# GSMMHM.net
KiCad netlist of a schematic drawn in Altium Designer
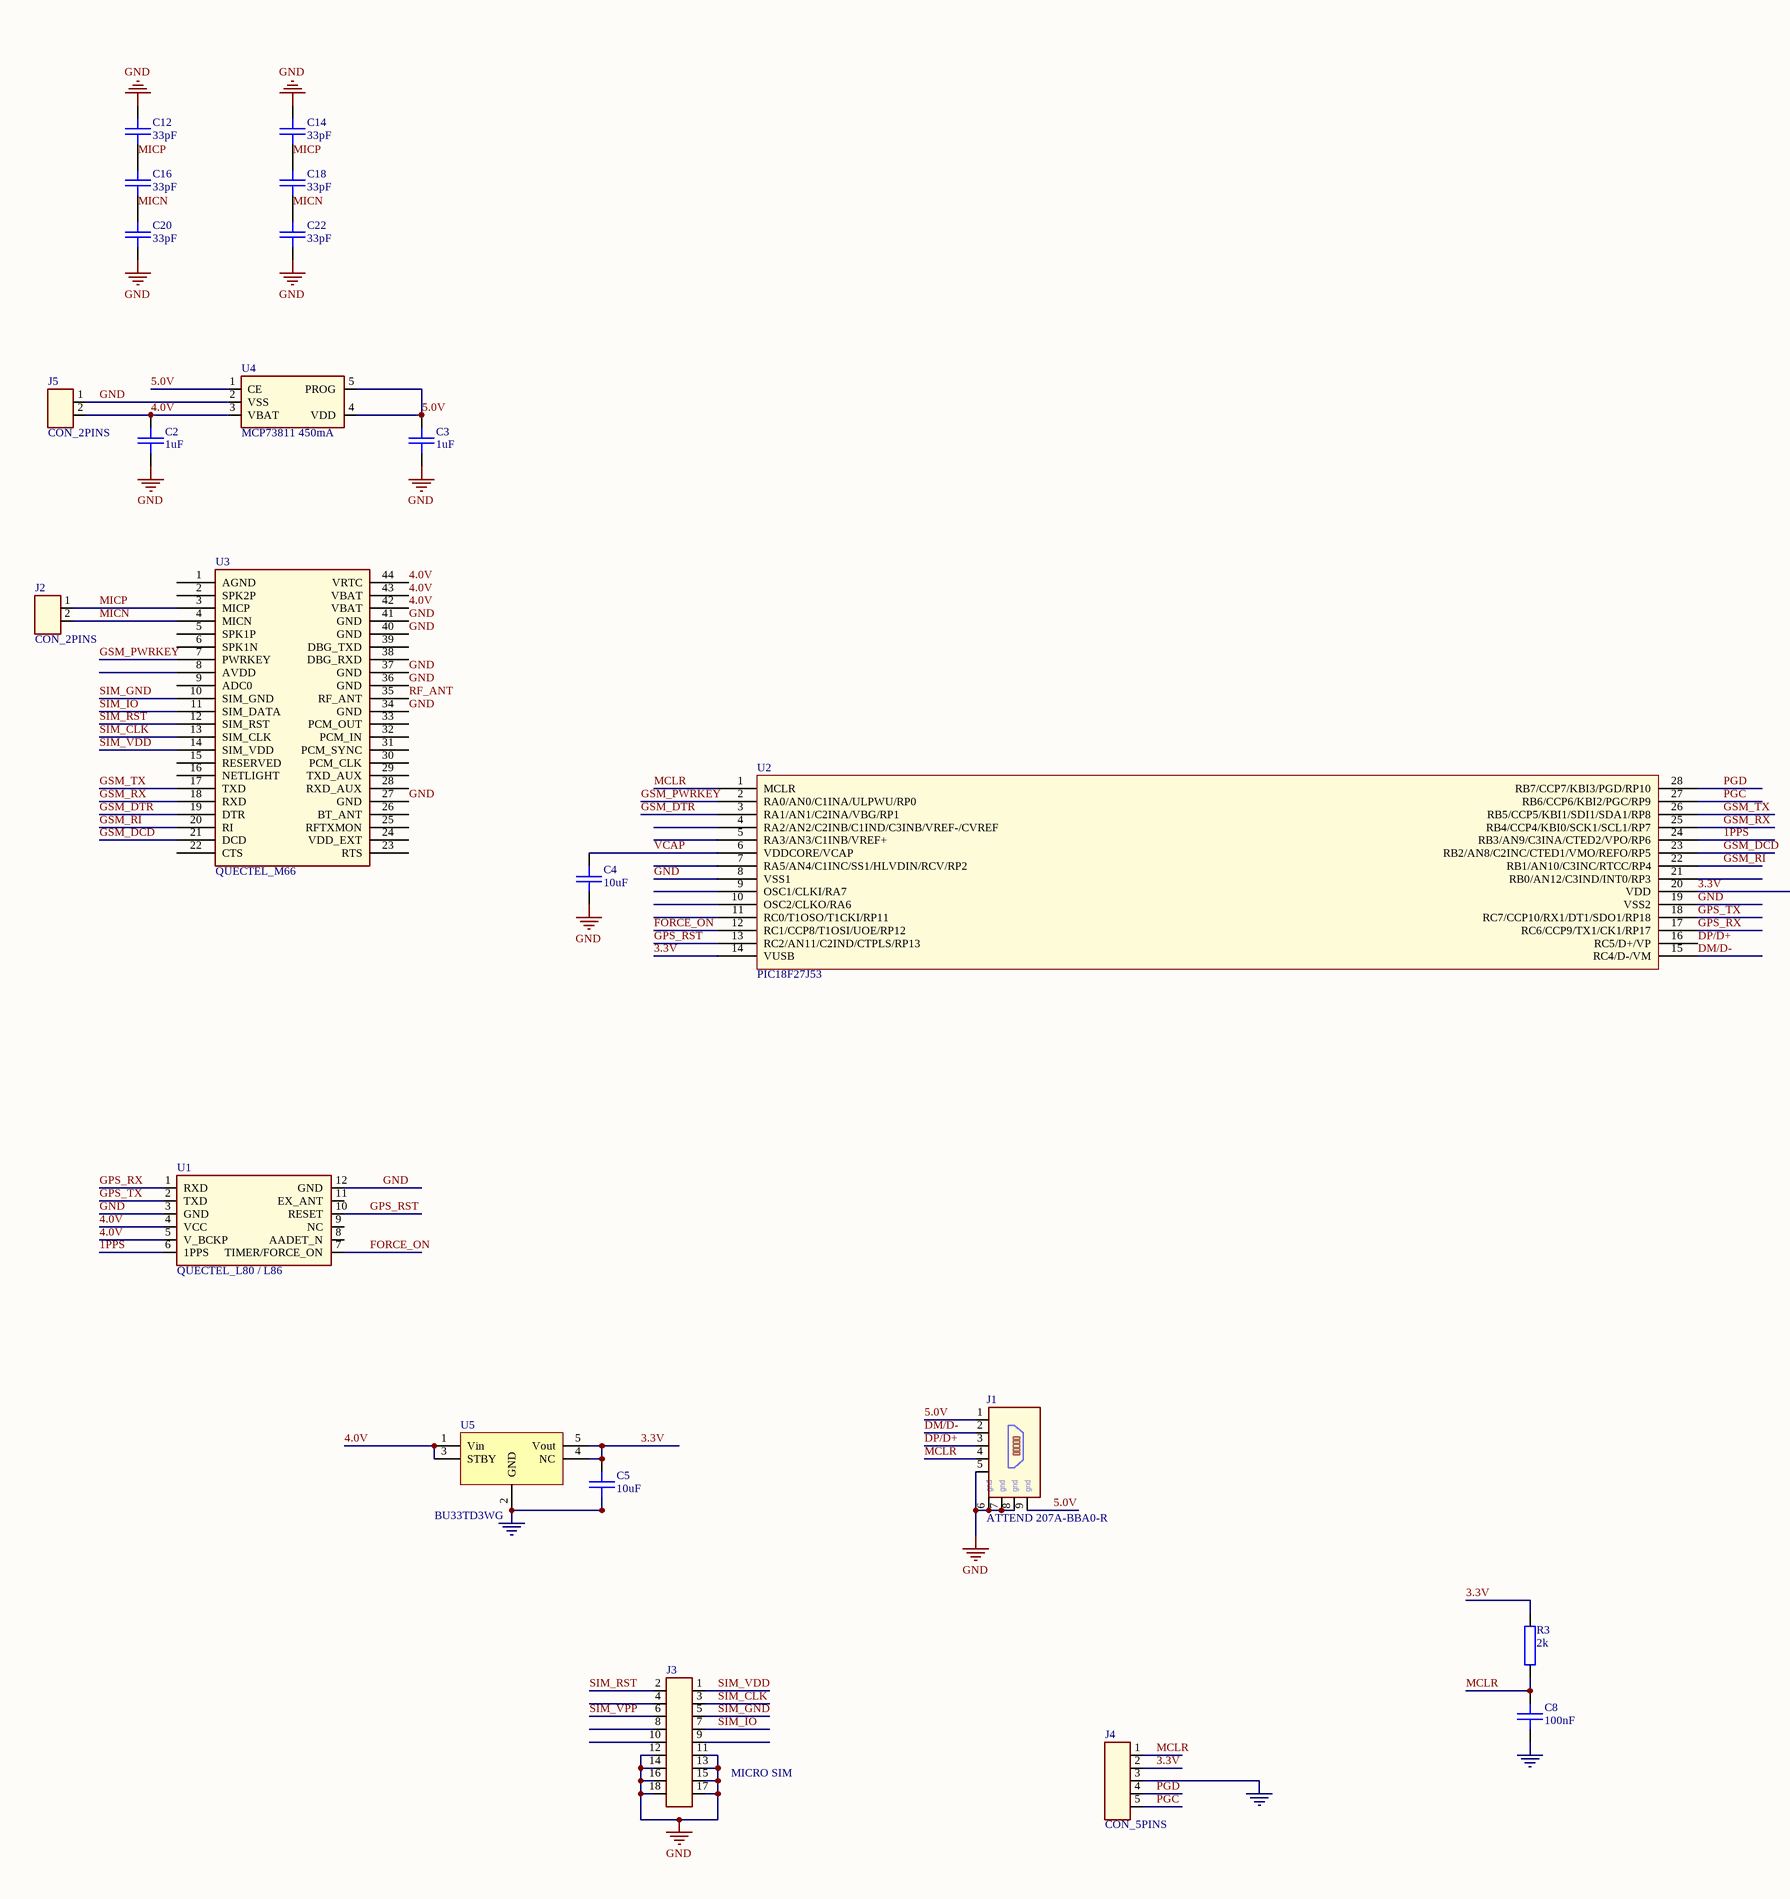
[diagram p0: GSMMHM.SchDoc, left]
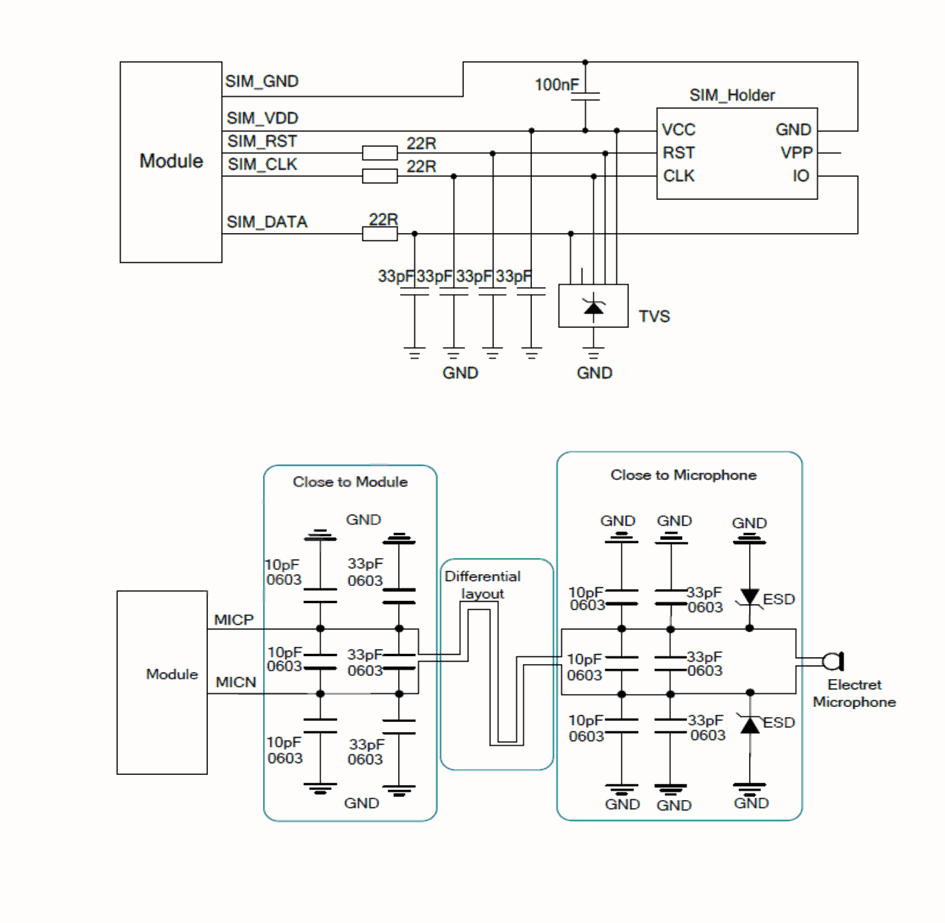
[diagram p1: GSMMHM.SchDoc, right]

(export (version "E")
  (design (tool "Eeschema 10.0.6"))
  (components
    (comp (ref "C2") (value "1uF") (footprint "SMD_0603_CAPC1608X95N") (libsource (lib "DLV") (part "C")))
    (comp (ref "C3") (value "1uF") (footprint "SMD_0603_CAPC1608X95N") (libsource (lib "DLV") (part "C")))
    (comp (ref "C4") (value "10uF") (footprint "SMD_0805_CAPC2012X95N") (libsource (lib "DLV") (part "C")))
    (comp (ref "C5") (value "10uF") (footprint "SMD_0805_CAPC2012X95N") (libsource (lib "DLV") (part "C")))
    (comp (ref "C8") (value "100nF") (footprint "SMD_0603_CAPC1608X95N") (libsource (lib "DLV") (part "C")))
    (comp (ref "C12") (value "33pF") (footprint "SMD_0603_CAPC1608X95N") (libsource (lib "DLV") (part "C")))
    (comp (ref "C14") (value "33pF") (footprint "SMD_0603_CAPC1608X95N") (libsource (lib "DLV") (part "C")))
    (comp (ref "C16") (value "33pF") (footprint "SMD_0603_CAPC1608X95N") (libsource (lib "DLV") (part "C")))
    (comp (ref "C18") (value "33pF") (footprint "SMD_0603_CAPC1608X95N") (libsource (lib "DLV") (part "C")))
    (comp (ref "C20") (value "33pF") (footprint "SMD_0603_CAPC1608X95N") (libsource (lib "DLV") (part "C")))
    (comp (ref "C22") (value "33pF") (footprint "SMD_0603_CAPC1608X95N") (libsource (lib "DLV") (part "C")))
    (comp (ref "J1")
      (value "ATTEND 207A-BBA0-R")
      (footprint "SMD_CON_MICRO_USB")
      (libsource (lib "DLV") (part "CON_USB_MINI"))
    )
    (comp (ref "J2")
      (value "CON_2PINS")
      (footprint "PTH_MIC_6MM_2.7MM_PITCH1.9")
      (libsource (lib "DLV") (part "CON_2PINS"))
    )
    (comp (ref "J3")
      (value "MICRO SIM")
      (footprint "SMD_CON-WURTH_MICRO_SIM_693021010811")
      (libsource (lib "DLV") (part "CON_2ROWS_18PINS"))
    )
    (comp (ref "J4") (value "CON_5PINS") (footprint "SIP5 - PGM") (libsource (lib "DLV") (part "CON_5PINS")))
    (comp (ref "J5")
      (value "CON_2PINS")
      (footprint "PTH_HDRV02W64P254_1X02")
      (libsource (lib "DLV") (part "CON_2PINS"))
    )
    (comp (ref "R3") (value "2k") (footprint "SMD_0603_RESC1608X55N") (libsource (lib "DLV") (part "R")))
    (comp (ref "U1")
      (value "QUECTEL_L80 / L86")
      (footprint "SMD_MOD_L80_SOIC254P1600X1600-12N")
      (libsource (lib "DLV") (part "MOD_QUECTEL_L80_L86"))
    )
    (comp (ref "U2")
      (value "PIC18F27J53")
      (footprint "SMD_SOP65P780X200-28N")
      (libsource (lib "DLV") (part "IC_PIC18F27J53"))
    )
    (comp (ref "U3")
      (value "QUECTEL_M66")
      (footprint "SMD_MOD_M66-44N")
      (libsource (lib "DLV") (part "MOD_QUECTEL_M66"))
    )
    (comp (ref "U4")
      (value "MCP73811 450mA")
      (footprint "SMD_SOT26_SOT95P285X140-5N - DLV")
      (description "MCP73812")
      (fields
        (field (name "DB_PART_NUMBER") "PSU000000127")
        (field (name "DB_MANUFACTURER_PART") "ROHM        BD33KA5WF-E2")
        (field (name "DB_APPROVED_BY") "VSN")
      )
      (libsource (lib "DLV") (part "IC_MCP73812"))
    )
    (comp (ref "U5")
      (value "BU33TD3WG")
      (footprint "SMD_SOT26_SOT95P285X140-5N - DLV")
      (libsource (lib "DLV") (part "IC_BU33TD3WG"))
    )
  )
  (nets
    (net (code "1") (name "/1PPS") (class "Default")
      (node (ref "U1") (pin "6") (pinfunction "1PPS_6") (pintype "passive"))
      (node (ref "U2") (pin "24") (pinfunction "RB3/AN9/C3INA/CTED2/VPO/RP6_24") (pintype "passive"))
    )
    (net (code "2") (name "/3.3V") (class "Default")
      (node (ref "C5") (pin "1") (pinfunction "1_1") (pintype "passive"))
      (node (ref "J4") (pin "2") (pinfunction "2_2") (pintype "passive"))
      (node (ref "R3") (pin "1") (pinfunction "1_1") (pintype "passive"))
      (node (ref "U2") (pin "14") (pinfunction "VUSB_14") (pintype "passive"))
      (node (ref "U2") (pin "20") (pinfunction "VDD_20") (pintype "passive"))
      (node (ref "U5") (pin "4") (pinfunction "NC_4") (pintype "passive"))
      (node (ref "U5") (pin "5") (pinfunction "Vout_5") (pintype "passive"))
    )
    (net (code "3") (name "/4.0V") (class "Default")
      (node (ref "C2") (pin "1") (pinfunction "1_1") (pintype "passive"))
      (node (ref "J5") (pin "2") (pinfunction "2_2") (pintype "passive"))
      (node (ref "U1") (pin "4") (pinfunction "VCC_4") (pintype "passive"))
      (node (ref "U1") (pin "5") (pinfunction "V_BCKP_5") (pintype "passive"))
      (node (ref "U3") (pin "42") (pinfunction "VBAT_42") (pintype "passive"))
      (node (ref "U3") (pin "43") (pinfunction "VBAT_43") (pintype "passive"))
      (node (ref "U3") (pin "44") (pinfunction "VRTC_44") (pintype "passive"))
      (node (ref "U4") (pin "3") (pinfunction "VBAT_3") (pintype "passive"))
      (node (ref "U5") (pin "1") (pinfunction "Vin_1") (pintype "passive"))
      (node (ref "U5") (pin "3") (pinfunction "STBY_3") (pintype "passive"))
    )
    (net (code "4") (name "/5.0V") (class "Default")
      (node (ref "C3") (pin "1") (pinfunction "1_1") (pintype "passive"))
      (node (ref "J1") (pin "1") (pinfunction "1_1") (pintype "passive"))
      (node (ref "J1") (pin "9") (pinfunction "9_9") (pintype "passive"))
      (node (ref "U4") (pin "1") (pinfunction "CE_1") (pintype "passive"))
      (node (ref "U4") (pin "4") (pinfunction "VDD_4") (pintype "passive"))
      (node (ref "U4") (pin "5") (pinfunction "PROG_5") (pintype "passive"))
    )
    (net (code "5") (name "/DM{slash}D-") (class "Default")
      (node (ref "J1") (pin "2") (pinfunction "2_2") (pintype "passive"))
      (node (ref "U2") (pin "15") (pinfunction "RC4/D-/VM_15") (pintype "passive"))
    )
    (net (code "6") (name "/DP{slash}D+") (class "Default")
      (node (ref "J1") (pin "3") (pinfunction "3_3") (pintype "passive"))
      (node (ref "U2") (pin "16") (pinfunction "RC5/D+/VP_16") (pintype "passive"))
    )
    (net (code "7") (name "/FORCE_ON") (class "Default")
      (node (ref "U1") (pin "7") (pinfunction "TIMER/FORCE_ON_7") (pintype "passive"))
      (node (ref "U2") (pin "12") (pinfunction "RC1/CCP8/T1OSI/UOE/RP12_12") (pintype "passive"))
    )
    (net (code "8") (name "/GPS_RST") (class "Default")
      (node (ref "U1") (pin "10") (pinfunction "RESET_10") (pintype "passive"))
      (node (ref "U2") (pin "13") (pinfunction "RC2/AN11/C2IND/CTPLS/RP13_13") (pintype "passive"))
    )
    (net (code "9") (name "/GPS_RX") (class "Default")
      (node (ref "U1") (pin "1") (pinfunction "RXD_1") (pintype "passive"))
      (node (ref "U2") (pin "17") (pinfunction "RC6/CCP9/TX1/CK1/RP17_17") (pintype "passive"))
    )
    (net (code "10") (name "/GPS_TX") (class "Default")
      (node (ref "U1") (pin "2") (pinfunction "TXD_2") (pintype "passive"))
      (node (ref "U2") (pin "18") (pinfunction "RC7/CCP10/RX1/DT1/SDO1/RP18_18") (pintype "passive"))
    )
    (net (code "11") (name "/GSM_DCD") (class "Default")
      (node (ref "U2") (pin "23") (pinfunction "RB2/AN8/C2INC/CTED1/VMO/REFO/RP5_23") (pintype "passive"))
      (node (ref "U3") (pin "21") (pinfunction "DCD_21") (pintype "passive"))
    )
    (net (code "12") (name "/GSM_DTR") (class "Default")
      (node (ref "U2") (pin "3") (pinfunction "RA1/AN1/C2INA/VBG/RP1_3") (pintype "passive"))
      (node (ref "U3") (pin "19") (pinfunction "DTR_19") (pintype "passive"))
    )
    (net (code "13") (name "/GSM_PWRKEY") (class "Default")
      (node (ref "U2") (pin "2") (pinfunction "RA0/AN0/C1INA/ULPWU/RP0_2") (pintype "passive"))
      (node (ref "U3") (pin "7") (pinfunction "PWRKEY_7") (pintype "passive"))
    )
    (net (code "14") (name "/GSM_RI") (class "Default")
      (node (ref "U2") (pin "22") (pinfunction "RB1/AN10/C3INC/RTCC/RP4_22") (pintype "passive"))
      (node (ref "U3") (pin "20") (pinfunction "RI_20") (pintype "passive"))
    )
    (net (code "15") (name "/GSM_RX") (class "Default")
      (node (ref "U2") (pin "25") (pinfunction "RB4/CCP4/KBI0/SCK1/SCL1/RP7_25") (pintype "passive"))
      (node (ref "U3") (pin "18") (pinfunction "RXD_18") (pintype "passive"))
    )
    (net (code "16") (name "/GSM_TX") (class "Default")
      (node (ref "U2") (pin "26") (pinfunction "RB5/CCP5/KBI1/SDI1/SDA1/RP8_26") (pintype "passive"))
      (node (ref "U3") (pin "17") (pinfunction "TXD_17") (pintype "passive"))
    )
    (net (code "17") (name "/MCLR") (class "Default")
      (node (ref "C8") (pin "1") (pinfunction "1_1") (pintype "passive"))
      (node (ref "J1") (pin "4") (pinfunction "4_4") (pintype "passive"))
      (node (ref "J4") (pin "1") (pinfunction "1_1") (pintype "passive"))
      (node (ref "R3") (pin "2") (pinfunction "2_2") (pintype "passive"))
      (node (ref "U2") (pin "1") (pinfunction "MCLR_1") (pintype "passive"))
    )
    (net (code "18") (name "/MICN") (class "Default")
      (node (ref "C16") (pin "2") (pinfunction "2_2") (pintype "passive"))
      (node (ref "C18") (pin "2") (pinfunction "2_2") (pintype "passive"))
      (node (ref "C20") (pin "1") (pinfunction "1_1") (pintype "passive"))
      (node (ref "C22") (pin "1") (pinfunction "1_1") (pintype "passive"))
      (node (ref "J2") (pin "2") (pinfunction "2_2") (pintype "passive"))
      (node (ref "U3") (pin "4") (pinfunction "MICN_4") (pintype "passive"))
    )
    (net (code "19") (name "/MICP") (class "Default")
      (node (ref "C12") (pin "2") (pinfunction "2_2") (pintype "passive"))
      (node (ref "C14") (pin "2") (pinfunction "2_2") (pintype "passive"))
      (node (ref "C16") (pin "1") (pinfunction "1_1") (pintype "passive"))
      (node (ref "C18") (pin "1") (pinfunction "1_1") (pintype "passive"))
      (node (ref "J2") (pin "1") (pinfunction "1_1") (pintype "passive"))
      (node (ref "U3") (pin "3") (pinfunction "MICP_3") (pintype "passive"))
    )
    (net (code "20") (name "/PGC") (class "Default")
      (node (ref "J4") (pin "5") (pinfunction "5_5") (pintype "passive"))
      (node (ref "U2") (pin "27") (pinfunction "RB6/CCP6/KBI2/PGC/RP9_27") (pintype "passive"))
    )
    (net (code "21") (name "/PGD") (class "Default")
      (node (ref "J4") (pin "4") (pinfunction "4_4") (pintype "passive"))
      (node (ref "U2") (pin "28") (pinfunction "RB7/CCP7/KBI3/PGD/RP10_28") (pintype "passive"))
    )
    (net (code "22") (name "/RF_ANT") (class "Default")
      (node (ref "U3") (pin "35") (pinfunction "RF_ANT_35") (pintype "passive"))
    )
    (net (code "23") (name "/SIM_CLK") (class "Default")
      (node (ref "J3") (pin "3") (pinfunction "3_3") (pintype "passive"))
      (node (ref "U3") (pin "13") (pinfunction "SIM_CLK_13") (pintype "passive"))
    )
    (net (code "24") (name "/SIM_GND") (class "Default")
      (node (ref "J3") (pin "5") (pinfunction "5_5") (pintype "passive"))
      (node (ref "U3") (pin "10") (pinfunction "SIM_GND_10") (pintype "passive"))
    )
    (net (code "25") (name "/SIM_IO") (class "Default")
      (node (ref "J3") (pin "7") (pinfunction "7_7") (pintype "passive"))
      (node (ref "U3") (pin "11") (pinfunction "SIM_DATA_11") (pintype "passive"))
    )
    (net (code "26") (name "/SIM_RST") (class "Default")
      (node (ref "J3") (pin "2") (pinfunction "2_2") (pintype "passive"))
      (node (ref "U3") (pin "12") (pinfunction "SIM_RST_12") (pintype "passive"))
    )
    (net (code "27") (name "/SIM_VDD") (class "Default")
      (node (ref "J3") (pin "1") (pinfunction "1_1") (pintype "passive"))
      (node (ref "U3") (pin "14") (pinfunction "SIM_VDD_14") (pintype "passive"))
    )
    (net (code "28") (name "/SIM_VPP") (class "Default")
      (node (ref "J3") (pin "6") (pinfunction "6_6") (pintype "passive"))
    )
    (net (code "29") (name "/VCAP") (class "Default")
      (node (ref "C4") (pin "1") (pinfunction "1_1") (pintype "passive"))
      (node (ref "U2") (pin "6") (pinfunction "VDDCORE/VCAP_6") (pintype "passive"))
    )
    (net (code "30") (name "GND") (class "Default")
      (node (ref "C12") (pin "1") (pinfunction "1_1") (pintype "passive"))
      (node (ref "C14") (pin "1") (pinfunction "1_1") (pintype "passive"))
      (node (ref "C2") (pin "2") (pinfunction "2_2") (pintype "passive"))
      (node (ref "C20") (pin "2") (pinfunction "2_2") (pintype "passive"))
      (node (ref "C22") (pin "2") (pinfunction "2_2") (pintype "passive"))
      (node (ref "C3") (pin "2") (pinfunction "2_2") (pintype "passive"))
      (node (ref "C4") (pin "2") (pinfunction "2_2") (pintype "passive"))
      (node (ref "C5") (pin "2") (pinfunction "2_2") (pintype "passive"))
      (node (ref "C8") (pin "2") (pinfunction "2_2") (pintype "passive"))
      (node (ref "J1") (pin "5") (pinfunction "5_5") (pintype "passive"))
      (node (ref "J1") (pin "6") (pinfunction "6_6") (pintype "passive"))
      (node (ref "J1") (pin "7") (pinfunction "7_7") (pintype "passive"))
      (node (ref "J1") (pin "8") (pinfunction "8_8") (pintype "passive"))
      (node (ref "J3") (pin "11") (pinfunction "11_11") (pintype "passive"))
      (node (ref "J3") (pin "12") (pinfunction "12_12") (pintype "passive"))
      (node (ref "J3") (pin "13") (pinfunction "13_13") (pintype "passive"))
      (node (ref "J3") (pin "14") (pinfunction "14_14") (pintype "passive"))
      (node (ref "J3") (pin "15") (pinfunction "15_15") (pintype "passive"))
      (node (ref "J3") (pin "16") (pinfunction "16_16") (pintype "passive"))
      (node (ref "J3") (pin "17") (pinfunction "17_17") (pintype "passive"))
      (node (ref "J3") (pin "18") (pinfunction "18_18") (pintype "passive"))
      (node (ref "J4") (pin "3") (pinfunction "3_3") (pintype "passive"))
      (node (ref "J5") (pin "1") (pinfunction "1_1") (pintype "passive"))
      (node (ref "U1") (pin "12") (pinfunction "GND_12") (pintype "passive"))
      (node (ref "U1") (pin "3") (pinfunction "GND_3") (pintype "passive"))
      (node (ref "U2") (pin "19") (pinfunction "VSS2_19") (pintype "passive"))
      (node (ref "U2") (pin "8") (pinfunction "VSS1_8") (pintype "passive"))
      (node (ref "U3") (pin "27") (pinfunction "GND_27") (pintype "passive"))
      (node (ref "U3") (pin "34") (pinfunction "GND_34") (pintype "passive"))
      (node (ref "U3") (pin "36") (pinfunction "GND_36") (pintype "passive"))
      (node (ref "U3") (pin "37") (pinfunction "GND_37") (pintype "passive"))
      (node (ref "U3") (pin "40") (pinfunction "GND_40") (pintype "passive"))
      (node (ref "U3") (pin "41") (pinfunction "GND_41") (pintype "passive"))
      (node (ref "U4") (pin "2") (pinfunction "VSS_2") (pintype "passive"))
      (node (ref "U5") (pin "2") (pinfunction "GND_2") (pintype "passive"))
    )
    (net (code "31") (name "unconnected-(J3-Pad4)") (class "Default")
      (node (ref "J3") (pin "4") (pinfunction "4_4") (pintype "passive"))
    )
    (net (code "32") (name "unconnected-(J3-Pad8)") (class "Default")
      (node (ref "J3") (pin "8") (pinfunction "8_8") (pintype "passive"))
    )
    (net (code "33") (name "unconnected-(J3-Pad9)") (class "Default")
      (node (ref "J3") (pin "9") (pinfunction "9_9") (pintype "passive"))
    )
    (net (code "34") (name "unconnected-(J3-Pad10)") (class "Default")
      (node (ref "J3") (pin "10") (pinfunction "10_10") (pintype "passive"))
    )
    (net (code "35") (name "unconnected-(U1-AADET_N-Pad8)") (class "Default")
      (node (ref "U1") (pin "8") (pinfunction "AADET_N_8") (pintype "passive"))
    )
    (net (code "36") (name "unconnected-(U1-EX_ANT-Pad11)") (class "Default")
      (node (ref "U1") (pin "11") (pinfunction "EX_ANT_11") (pintype "passive"))
    )
    (net (code "37") (name "unconnected-(U1-NC-Pad9)") (class "Default")
      (node (ref "U1") (pin "9") (pinfunction "NC_9") (pintype "passive"))
    )
    (net (code "38") (name "unconnected-(U2-OSC1{slash}CLKI{slash}RA7-Pad9)") (class "Default")
      (node (ref "U2") (pin "9") (pinfunction "OSC1/CLKI/RA7_9") (pintype "passive"))
    )
    (net (code "39") (name "unconnected-(U2-OSC2{slash}CLKO{slash}RA6-Pad10)") (class "Default")
      (node (ref "U2") (pin "10") (pinfunction "OSC2/CLKO/RA6_10") (pintype "passive"))
    )
    (net (code "40") (name "unconnected-(U2-RA2{slash}AN2{slash}C2INB{slash}C1IND{slash}C3INB{slash}VREF-{slash}CVREF-Pad4)") (class "Default")
      (node (ref "U2") (pin "4") (pinfunction "RA2/AN2/C2INB/C1IND/C3INB/VREF-/CVREF_4") (pintype "passive"))
    )
    (net (code "41") (name "unconnected-(U2-RA3{slash}AN3{slash}C1INB{slash}VREF+-Pad5)") (class "Default")
      (node (ref "U2") (pin "5") (pinfunction "RA3/AN3/C1INB/VREF+_5") (pintype "passive"))
    )
    (net (code "42") (name "unconnected-(U2-RA5{slash}AN4{slash}C1INC{slash}SS1{slash}HLVDIN{slash}RCV{slash}RP2-Pad7)") (class "Default")
      (node (ref "U2") (pin "7") (pinfunction "RA5/AN4/C1INC/SS1/HLVDIN/RCV/RP2_7") (pintype "passive"))
    )
    (net (code "43") (name "unconnected-(U2-RB0{slash}AN12{slash}C3IND{slash}INT0{slash}RP3-Pad21)") (class "Default")
      (node (ref "U2") (pin "21") (pinfunction "RB0/AN12/C3IND/INT0/RP3_21") (pintype "passive"))
    )
    (net (code "44") (name "unconnected-(U2-RC0{slash}T1OSO{slash}T1CKI{slash}RP11-Pad11)") (class "Default")
      (node (ref "U2") (pin "11") (pinfunction "RC0/T1OSO/T1CKI/RP11_11") (pintype "passive"))
    )
    (net (code "45") (name "unconnected-(U3-ADC0-Pad9)") (class "Default")
      (node (ref "U3") (pin "9") (pinfunction "ADC0_9") (pintype "passive"))
    )
    (net (code "46") (name "unconnected-(U3-AGND-Pad1)") (class "Default")
      (node (ref "U3") (pin "1") (pinfunction "AGND_1") (pintype "passive"))
    )
    (net (code "47") (name "unconnected-(U3-AVDD-Pad8)") (class "Default")
      (node (ref "U3") (pin "8") (pinfunction "AVDD_8") (pintype "passive"))
    )
    (net (code "48") (name "unconnected-(U3-BT_ANT-Pad26)") (class "Default")
      (node (ref "U3") (pin "26") (pinfunction "BT_ANT_26") (pintype "passive"))
    )
    (net (code "49") (name "unconnected-(U3-CTS-Pad22)") (class "Default")
      (node (ref "U3") (pin "22") (pinfunction "CTS_22") (pintype "passive"))
    )
    (net (code "50") (name "unconnected-(U3-DBG_RXD-Pad38)") (class "Default")
      (node (ref "U3") (pin "38") (pinfunction "DBG_RXD_38") (pintype "passive"))
    )
    (net (code "51") (name "unconnected-(U3-DBG_TXD-Pad39)") (class "Default")
      (node (ref "U3") (pin "39") (pinfunction "DBG_TXD_39") (pintype "passive"))
    )
    (net (code "52") (name "unconnected-(U3-NETLIGHT-Pad16)") (class "Default")
      (node (ref "U3") (pin "16") (pinfunction "NETLIGHT_16") (pintype "passive"))
    )
    (net (code "53") (name "unconnected-(U3-PCM_CLK-Pad30)") (class "Default")
      (node (ref "U3") (pin "30") (pinfunction "PCM_CLK_30") (pintype "passive"))
    )
    (net (code "54") (name "unconnected-(U3-PCM_IN-Pad32)") (class "Default")
      (node (ref "U3") (pin "32") (pinfunction "PCM_IN_32") (pintype "passive"))
    )
    (net (code "55") (name "unconnected-(U3-PCM_OUT-Pad33)") (class "Default")
      (node (ref "U3") (pin "33") (pinfunction "PCM_OUT_33") (pintype "passive"))
    )
    (net (code "56") (name "unconnected-(U3-PCM_SYNC-Pad31)") (class "Default")
      (node (ref "U3") (pin "31") (pinfunction "PCM_SYNC_31") (pintype "passive"))
    )
    (net (code "57") (name "unconnected-(U3-RESERVED-Pad15)") (class "Default")
      (node (ref "U3") (pin "15") (pinfunction "RESERVED_15") (pintype "passive"))
    )
    (net (code "58") (name "unconnected-(U3-RFTXMON-Pad25)") (class "Default")
      (node (ref "U3") (pin "25") (pinfunction "RFTXMON_25") (pintype "passive"))
    )
    (net (code "59") (name "unconnected-(U3-RTS-Pad23)") (class "Default")
      (node (ref "U3") (pin "23") (pinfunction "RTS_23") (pintype "passive"))
    )
    (net (code "60") (name "unconnected-(U3-RXD_AUX-Pad28)") (class "Default")
      (node (ref "U3") (pin "28") (pinfunction "RXD_AUX_28") (pintype "passive"))
    )
    (net (code "61") (name "unconnected-(U3-SPK1N-Pad6)") (class "Default")
      (node (ref "U3") (pin "6") (pinfunction "SPK1N_6") (pintype "passive"))
    )
    (net (code "62") (name "unconnected-(U3-SPK1P-Pad5)") (class "Default")
      (node (ref "U3") (pin "5") (pinfunction "SPK1P_5") (pintype "passive"))
    )
    (net (code "63") (name "unconnected-(U3-SPK2P-Pad2)") (class "Default")
      (node (ref "U3") (pin "2") (pinfunction "SPK2P_2") (pintype "passive"))
    )
    (net (code "64") (name "unconnected-(U3-TXD_AUX-Pad29)") (class "Default")
      (node (ref "U3") (pin "29") (pinfunction "TXD_AUX_29") (pintype "passive"))
    )
    (net (code "65") (name "unconnected-(U3-VDD_EXT-Pad24)") (class "Default")
      (node (ref "U3") (pin "24") (pinfunction "VDD_EXT_24") (pintype "passive"))
    )
  )
)
